# Arduino_FPGA_SPI_MUX.net
KiCad netlist of a schematic drawn in Altium Designer
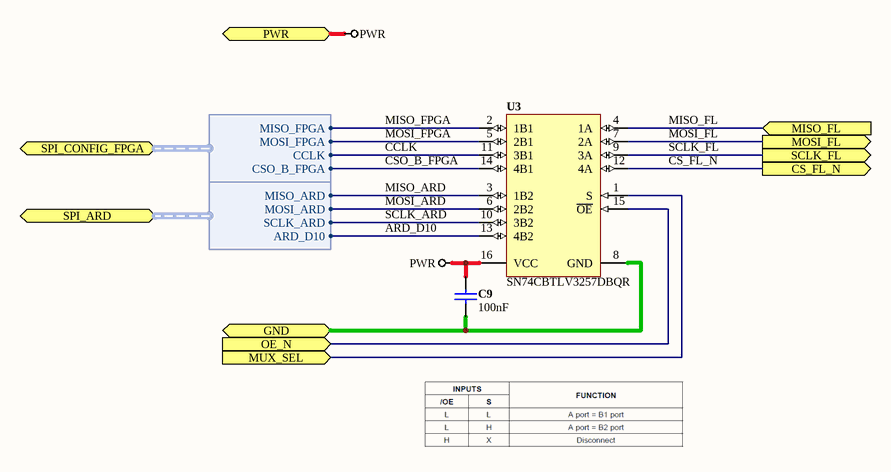
[diagram p0: Arduino FPGA SPI MUX.SchDoc]

(export (version "E")
  (design (tool "Eeschema 10.0.6"))
  (components
    (comp (ref "C9")
      (value "100nF")
      (footprint "CAPC0402(1005)60_L")
      (fields
        (field (name "TOLERANCE") "±10%")
        (field (name "MANUFACTURER PART NUMBER") "C0402C104K8PACTU")
        (field (name "Comment") "CAP 100nF 16V 0402(1005)")
      )
      (libsource (lib "Component_Database") (part "CAP_NP"))
    )
    (comp (ref "U3")
      (value "SN74CBTLV3257DBQR")
      (footprint "DBQ16")
      (description "Low-Voltage 4-Bit 1-Of-2 FET Multiplexer/Demultiplexer, 16-pin SOP (DBQ16)")
      (libsource (lib "FPGA-pcie") (part "SN74CBTLV3257DBQR"))
    )
  )
  (nets
    (net (code "3") (name "/ARD_D10") (class "Default")
      (node (ref "U3") (pin "13") (pinfunction "4B2_13") (pintype "bidirectional"))
    )
    (net (code "4") (name "/CCLK") (class "Default")
      (node (ref "U3") (pin "11") (pinfunction "3B1_11") (pintype "bidirectional"))
    )
    (net (code "5") (name "/CSO_B_FPGA") (class "Default")
      (node (ref "U3") (pin "14") (pinfunction "4B1_14") (pintype "bidirectional"))
    )
    (net (code "6") (name "/CS_FL_N") (class "Default")
      (node (ref "U3") (pin "12") (pinfunction "4A_12") (pintype "bidirectional"))
    )
    (net (code "7") (name "/GND") (class "Default")
      (node (ref "C9") (pin "2") (pinfunction "2_2") (pintype "passive"))
      (node (ref "U3") (pin "8") (pinfunction "GND_8") (pintype "power_in"))
    )
    (net (code "8") (name "/MISO_ARD") (class "Default")
      (node (ref "U3") (pin "3") (pinfunction "1B2_3") (pintype "bidirectional"))
    )
    (net (code "9") (name "/MISO_FL") (class "Default")
      (node (ref "U3") (pin "4") (pinfunction "1A_4") (pintype "bidirectional"))
    )
    (net (code "10") (name "/MISO_FPGA") (class "Default")
      (node (ref "U3") (pin "2") (pinfunction "1B1_2") (pintype "bidirectional"))
    )
    (net (code "11") (name "/MOSI_ARD") (class "Default")
      (node (ref "U3") (pin "6") (pinfunction "2B2_6") (pintype "bidirectional"))
    )
    (net (code "12") (name "/MOSI_FL") (class "Default")
      (node (ref "U3") (pin "7") (pinfunction "2A_7") (pintype "bidirectional"))
    )
    (net (code "13") (name "/MOSI_FPGA") (class "Default")
      (node (ref "U3") (pin "5") (pinfunction "2B1_5") (pintype "bidirectional"))
    )
    (net (code "14") (name "/MUX_SEL") (class "Default")
      (node (ref "U3") (pin "1") (pinfunction "S_1") (pintype "input"))
    )
    (net (code "15") (name "/OE_N") (class "Default")
      (node (ref "U3") (pin "15") (pinfunction "~{OE}_15") (pintype "input"))
    )
    (net (code "16") (name "/SCLK_ARD") (class "Default")
      (node (ref "U3") (pin "10") (pinfunction "3B2_10") (pintype "bidirectional"))
    )
    (net (code "17") (name "/SCLK_FL") (class "Default")
      (node (ref "U3") (pin "9") (pinfunction "3A_9") (pintype "bidirectional"))
    )
    (net (code "20") (name "PWR") (class "Default")
      (node (ref "C9") (pin "1") (pinfunction "1_1") (pintype "passive"))
      (node (ref "U3") (pin "16") (pinfunction "VCC_16") (pintype "power_in"))
    )
  )
)
